# A604X.net
KiCad netlist of a schematic drawn in EAGLE
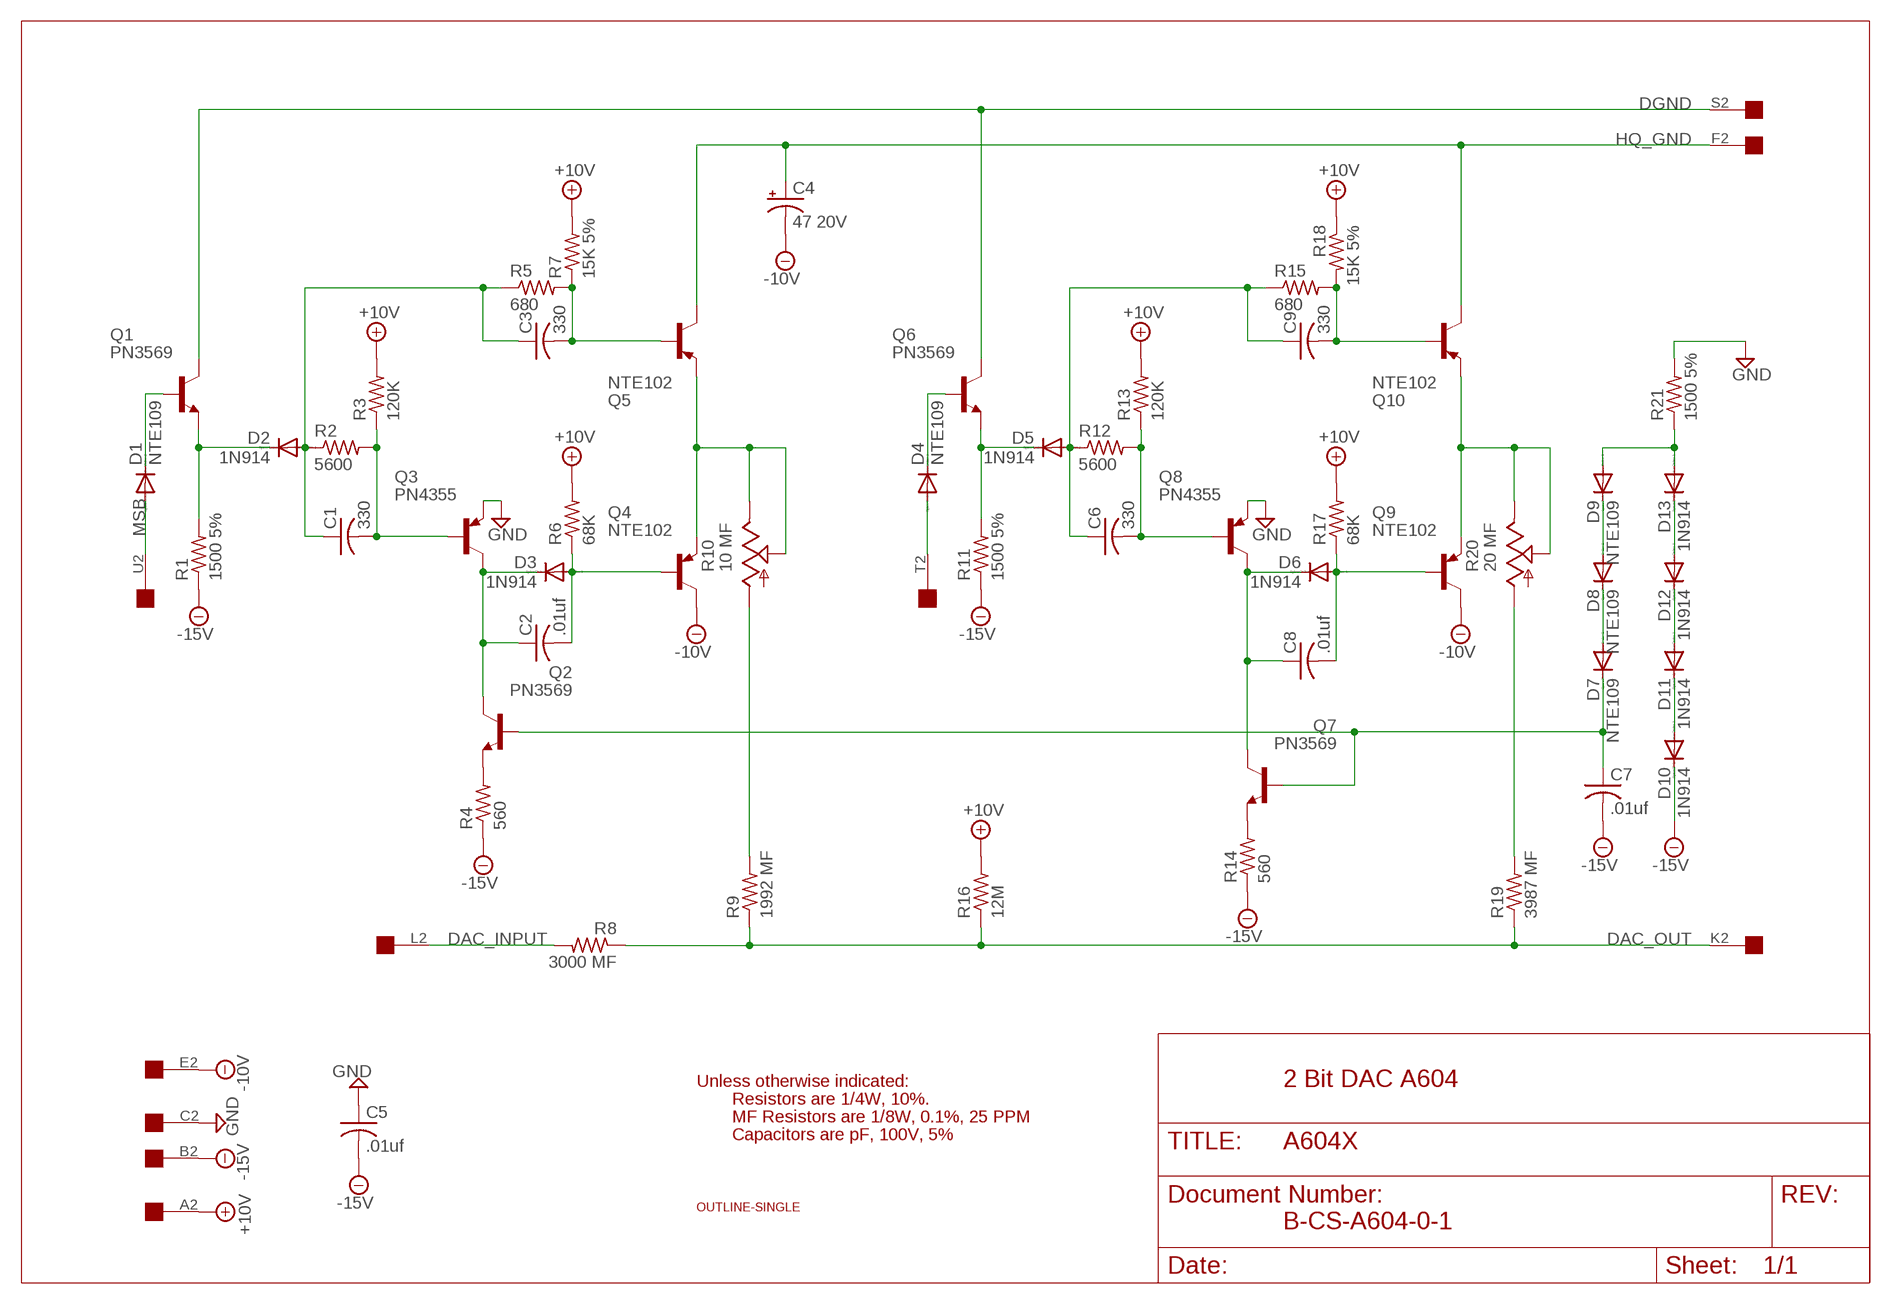
[diagram p0: schematic, sheet 1]

(export (version "E")
  (design (tool "Eeschema 10.0.6"))
  (components
    (comp (ref "C1")
      (value "330")
      (footprint "eagle-import:C075-032X103")
      (libsource (lib "eagle-import") (part "C-US075-032X103"))
    )
    (comp (ref "C2")
      (value ".01uf")
      (footprint "eagle-import:C050-025X075")
      (libsource (lib "eagle-import") (part "C-US050-025X075"))
    )
    (comp (ref "C3")
      (value "330")
      (footprint "eagle-import:C075-032X103")
      (libsource (lib "eagle-import") (part "C-US075-032X103"))
    )
    (comp (ref "C4")
      (value "47 20V")
      (footprint "eagle-import:E22-6")
      (libsource (lib "eagle-import") (part "CPOL-USE22-6AXIAL"))
    )
    (comp (ref "C5")
      (value ".01uf")
      (footprint "eagle-import:C050-025X075")
      (libsource (lib "eagle-import") (part "C-US050-025X075"))
    )
    (comp (ref "C6")
      (value "330")
      (footprint "eagle-import:C075-032X103")
      (libsource (lib "eagle-import") (part "C-US075-032X103"))
    )
    (comp (ref "C7")
      (value ".01uf")
      (footprint "eagle-import:C050-025X075")
      (libsource (lib "eagle-import") (part "C-US050-025X075"))
    )
    (comp (ref "C8")
      (value ".01uf")
      (footprint "eagle-import:C050-025X075")
      (libsource (lib "eagle-import") (part "C-US050-025X075"))
    )
    (comp (ref "C9")
      (value "330")
      (footprint "eagle-import:C075-032X103")
      (libsource (lib "eagle-import") (part "C-US075-032X103"))
    )
    (comp (ref "D1")
      (value "NTE109")
      (footprint "eagle-import:DO35-10")
      (libsource (lib "eagle-import") (part "1N4148DO35-10"))
    )
    (comp (ref "D2")
      (value "1N914")
      (footprint "eagle-import:DO35-10")
      (libsource (lib "eagle-import") (part "1N4148DO35-10"))
    )
    (comp (ref "D3")
      (value "1N914")
      (footprint "eagle-import:DO35-10")
      (libsource (lib "eagle-import") (part "1N4148DO35-10"))
    )
    (comp (ref "D4")
      (value "NTE109")
      (footprint "eagle-import:DO35-10")
      (libsource (lib "eagle-import") (part "1N4148DO35-10"))
    )
    (comp (ref "D5")
      (value "1N914")
      (footprint "eagle-import:DO35-10")
      (libsource (lib "eagle-import") (part "1N4148DO35-10"))
    )
    (comp (ref "D6")
      (value "1N914")
      (footprint "eagle-import:DO35-10")
      (libsource (lib "eagle-import") (part "1N4148DO35-10"))
    )
    (comp (ref "D7")
      (value "NTE109")
      (footprint "eagle-import:DO35-10")
      (libsource (lib "eagle-import") (part "1N4148DO35-10"))
    )
    (comp (ref "D8")
      (value "NTE109")
      (footprint "eagle-import:DO35-10")
      (libsource (lib "eagle-import") (part "1N4148DO35-10"))
    )
    (comp (ref "D9")
      (value "NTE109")
      (footprint "eagle-import:DO35-10")
      (libsource (lib "eagle-import") (part "1N4148DO35-10"))
    )
    (comp (ref "D10")
      (value "1N914")
      (footprint "eagle-import:DO35-10")
      (libsource (lib "eagle-import") (part "1N4148DO35-10"))
    )
    (comp (ref "D11")
      (value "1N914")
      (footprint "eagle-import:DO35-10")
      (libsource (lib "eagle-import") (part "1N4148DO35-10"))
    )
    (comp (ref "D12")
      (value "1N914")
      (footprint "eagle-import:DO35-10")
      (libsource (lib "eagle-import") (part "1N4148DO35-10"))
    )
    (comp (ref "D13")
      (value "1N914")
      (footprint "eagle-import:DO35-10")
      (libsource (lib "eagle-import") (part "1N4148DO35-10"))
    )
    (comp (ref "Q1")
      (value "PN3569")
      (footprint "eagle-import:TO39")
      (libsource (lib "eagle-import") (part "-NPN-TO39-EBC2N1613"))
    )
    (comp (ref "Q2")
      (value "PN3569")
      (footprint "eagle-import:TO39")
      (libsource (lib "eagle-import") (part "-NPN-TO39-EBC2N1613"))
    )
    (comp (ref "Q3")
      (value "PN4355")
      (footprint "eagle-import:TO39")
      (libsource (lib "eagle-import") (part "2N2904A"))
    )
    (comp (ref "Q4")
      (value "NTE102")
      (footprint "eagle-import:TO39")
      (libsource (lib "eagle-import") (part "2N2904A"))
    )
    (comp (ref "Q5")
      (value "NTE102")
      (footprint "eagle-import:TO39")
      (libsource (lib "eagle-import") (part "2N2904A"))
    )
    (comp (ref "Q6")
      (value "PN3569")
      (footprint "eagle-import:TO39")
      (libsource (lib "eagle-import") (part "-NPN-TO39-EBC2N1613"))
    )
    (comp (ref "Q7")
      (value "PN3569")
      (footprint "eagle-import:TO39")
      (libsource (lib "eagle-import") (part "-NPN-TO39-EBC2N1613"))
    )
    (comp (ref "Q8")
      (value "PN4355")
      (footprint "eagle-import:TO39")
      (libsource (lib "eagle-import") (part "2N2904A"))
    )
    (comp (ref "Q9")
      (value "NTE102")
      (footprint "eagle-import:TO39")
      (libsource (lib "eagle-import") (part "2N2904A"))
    )
    (comp (ref "Q10")
      (value "NTE102")
      (footprint "eagle-import:TO39")
      (libsource (lib "eagle-import") (part "2N2904A"))
    )
    (comp (ref "R1")
      (value "1500 5%")
      (footprint "eagle-import:0207_10")
      (libsource (lib "eagle-import") (part "R-US_0207/10"))
    )
    (comp (ref "R2")
      (value "5600")
      (footprint "eagle-import:0207_10")
      (libsource (lib "eagle-import") (part "R-US_0207/10"))
    )
    (comp (ref "R3")
      (value "120K")
      (footprint "eagle-import:0207_10")
      (libsource (lib "eagle-import") (part "R-US_0207/10"))
    )
    (comp (ref "R4")
      (value "560")
      (footprint "eagle-import:0207_10")
      (libsource (lib "eagle-import") (part "R-US_0207/10"))
    )
    (comp (ref "R5")
      (value "680")
      (footprint "eagle-import:0207_10")
      (libsource (lib "eagle-import") (part "R-US_0207/10"))
    )
    (comp (ref "R6")
      (value "68K")
      (footprint "eagle-import:0207_10")
      (libsource (lib "eagle-import") (part "R-US_0207/10"))
    )
    (comp (ref "R7")
      (value "15K 5%")
      (footprint "eagle-import:0207_10")
      (libsource (lib "eagle-import") (part "R-US_0207/10"))
    )
    (comp (ref "R8")
      (value "3000 MF")
      (footprint "eagle-import:0309_12")
      (libsource (lib "eagle-import") (part "R-US_0309/12"))
    )
    (comp (ref "R9")
      (value "1992 MF")
      (footprint "eagle-import:0309_12")
      (libsource (lib "eagle-import") (part "R-US_0309/12"))
    )
    (comp (ref "R10")
      (value "10 MF")
      (footprint "eagle-import:S75P")
      (libsource (lib "eagle-import") (part "TRIM_US-S75P"))
    )
    (comp (ref "R11")
      (value "1500 5%")
      (footprint "eagle-import:0207_10")
      (libsource (lib "eagle-import") (part "R-US_0207/10"))
    )
    (comp (ref "R12")
      (value "5600")
      (footprint "eagle-import:0207_10")
      (libsource (lib "eagle-import") (part "R-US_0207/10"))
    )
    (comp (ref "R13")
      (value "120K")
      (footprint "eagle-import:0207_10")
      (libsource (lib "eagle-import") (part "R-US_0207/10"))
    )
    (comp (ref "R14")
      (value "560")
      (footprint "eagle-import:0207_10")
      (libsource (lib "eagle-import") (part "R-US_0207/10"))
    )
    (comp (ref "R15")
      (value "680")
      (footprint "eagle-import:0207_10")
      (libsource (lib "eagle-import") (part "R-US_0207/10"))
    )
    (comp (ref "R16")
      (value "12M")
      (footprint "eagle-import:0207_10")
      (libsource (lib "eagle-import") (part "R-US_0207/10"))
    )
    (comp (ref "R17")
      (value "68K")
      (footprint "eagle-import:0207_10")
      (libsource (lib "eagle-import") (part "R-US_0207/10"))
    )
    (comp (ref "R18")
      (value "15K 5%")
      (footprint "eagle-import:0207_10")
      (libsource (lib "eagle-import") (part "R-US_0207/10"))
    )
    (comp (ref "R19")
      (value "3987 MF")
      (footprint "eagle-import:0309_12")
      (libsource (lib "eagle-import") (part "R-US_0309/12"))
    )
    (comp (ref "R20")
      (value "20 MF")
      (footprint "eagle-import:S75P")
      (libsource (lib "eagle-import") (part "TRIM_US-S75P"))
    )
    (comp (ref "R21")
      (value "1500 5%")
      (footprint "eagle-import:0207_10")
      (libsource (lib "eagle-import") (part "R-US_0207/10"))
    )
    (comp (ref "U$1")
      (value "OUTLINE-SINGLE")
      (footprint "eagle-import:SINGLE")
      (libsource (lib "eagle-import") (part "OUTLINE-SINGLE"))
    )
    (comp (ref "U$3")
      (value "EDGE-1")
      (footprint "eagle-import:EDGE-CON1")
      (libsource (lib "eagle-import") (part "EDGE-1"))
    )
  )
  (nets
    (net (code "1") (name "+10V") (class "Default")
      (node (ref "R13") (pin "2") (pinfunction "2_2") (pintype "passive"))
      (node (ref "R16") (pin "2") (pinfunction "2_2") (pintype "passive"))
      (node (ref "R17") (pin "2") (pinfunction "2_2") (pintype "passive"))
      (node (ref "R18") (pin "1") (pinfunction "1_1") (pintype "passive"))
      (node (ref "R3") (pin "2") (pinfunction "2_2") (pintype "passive"))
      (node (ref "R6") (pin "2") (pinfunction "2_2") (pintype "passive"))
      (node (ref "R7") (pin "2") (pinfunction "2_2") (pintype "passive"))
      (node (ref "U$3") (pin "A2") (pinfunction "1_A2") (pintype "bidirectional"))
    )
    (net (code "2") (name "-10V") (class "Default")
      (node (ref "C4") (pin "-") (pinfunction "-_-") (pintype "passive"))
      (node (ref "Q4") (pin "3") (pinfunction "C_3") (pintype "passive"))
      (node (ref "Q9") (pin "3") (pinfunction "C_3") (pintype "passive"))
      (node (ref "U$3") (pin "E2") (pinfunction "1_E2") (pintype "bidirectional"))
    )
    (net (code "3") (name "-15V") (class "Default")
      (node (ref "C5") (pin "2") (pinfunction "2_2") (pintype "passive"))
      (node (ref "C7") (pin "2") (pinfunction "2_2") (pintype "passive"))
      (node (ref "D10") (pin "C") (pinfunction "C_C") (pintype "passive"))
      (node (ref "R1") (pin "1") (pinfunction "1_1") (pintype "passive"))
      (node (ref "R11") (pin "1") (pinfunction "1_1") (pintype "passive"))
      (node (ref "R14") (pin "1") (pinfunction "1_1") (pintype "passive"))
      (node (ref "R4") (pin "1") (pinfunction "1_1") (pintype "passive"))
      (node (ref "U$3") (pin "B2") (pinfunction "1_B2") (pintype "bidirectional"))
    )
    (net (code "4") (name "/DAC_INPUT") (class "Default")
      (node (ref "R8") (pin "2") (pinfunction "2_2") (pintype "passive"))
      (node (ref "U$3") (pin "L2") (pinfunction "1_L2") (pintype "bidirectional"))
    )
    (net (code "5") (name "/DAC_OUT") (class "Default")
      (node (ref "R16") (pin "1") (pinfunction "1_1") (pintype "passive"))
      (node (ref "R19") (pin "1") (pinfunction "1_1") (pintype "passive"))
      (node (ref "R8") (pin "1") (pinfunction "1_1") (pintype "passive"))
      (node (ref "R9") (pin "1") (pinfunction "1_1") (pintype "passive"))
      (node (ref "U$3") (pin "K2") (pinfunction "1_K2") (pintype "bidirectional"))
    )
    (net (code "6") (name "/DGND") (class "Default")
      (node (ref "Q1") (pin "3") (pinfunction "C_3") (pintype "passive"))
      (node (ref "Q6") (pin "3") (pinfunction "C_3") (pintype "passive"))
      (node (ref "U$3") (pin "S2") (pinfunction "1_S2") (pintype "bidirectional"))
    )
    (net (code "7") (name "/HQ_GND") (class "Default")
      (node (ref "C4") (pin "+") (pinfunction "+_+") (pintype "passive"))
      (node (ref "Q10") (pin "3") (pinfunction "C_3") (pintype "passive"))
      (node (ref "Q5") (pin "3") (pinfunction "C_3") (pintype "passive"))
      (node (ref "U$3") (pin "F2") (pinfunction "1_F2") (pintype "bidirectional"))
    )
    (net (code "8") (name "/MSB") (class "Default")
      (node (ref "D1") (pin "A") (pinfunction "A_A") (pintype "passive"))
      (node (ref "U$3") (pin "U2") (pinfunction "1_U2") (pintype "bidirectional"))
    )
    (net (code "9") (name "GND") (class "Default")
      (node (ref "C5") (pin "1") (pinfunction "1_1") (pintype "passive"))
      (node (ref "Q3") (pin "1") (pinfunction "E_1") (pintype "passive"))
      (node (ref "Q8") (pin "1") (pinfunction "E_1") (pintype "passive"))
      (node (ref "R21") (pin "2") (pinfunction "2_2") (pintype "passive"))
      (node (ref "U$3") (pin "C2") (pinfunction "1_C2") (pintype "bidirectional"))
    )
    (net (code "10") (name "Net-(C1-Pad1)") (class "Default")
      (node (ref "C1") (pin "1") (pinfunction "1_1") (pintype "passive"))
      (node (ref "C3") (pin "1") (pinfunction "1_1") (pintype "passive"))
      (node (ref "D2") (pin "A") (pinfunction "A_A") (pintype "passive"))
      (node (ref "R2") (pin "1") (pinfunction "1_1") (pintype "passive"))
      (node (ref "R5") (pin "1") (pinfunction "1_1") (pintype "passive"))
    )
    (net (code "11") (name "Net-(C6-Pad1)") (class "Default")
      (node (ref "C6") (pin "1") (pinfunction "1_1") (pintype "passive"))
      (node (ref "C9") (pin "1") (pinfunction "1_1") (pintype "passive"))
      (node (ref "D5") (pin "A") (pinfunction "A_A") (pintype "passive"))
      (node (ref "R12") (pin "1") (pinfunction "1_1") (pintype "passive"))
      (node (ref "R15") (pin "1") (pinfunction "1_1") (pintype "passive"))
    )
    (net (code "12") (name "Net-(D7-PadA)") (class "Default")
      (node (ref "D7") (pin "A") (pinfunction "A_A") (pintype "passive"))
      (node (ref "D8") (pin "C") (pinfunction "C_C") (pintype "passive"))
    )
    (net (code "13") (name "Net-(D8-PadA)") (class "Default")
      (node (ref "D8") (pin "A") (pinfunction "A_A") (pintype "passive"))
      (node (ref "D9") (pin "C") (pinfunction "C_C") (pintype "passive"))
    )
    (net (code "14") (name "Net-(D10-PadA)") (class "Default")
      (node (ref "D10") (pin "A") (pinfunction "A_A") (pintype "passive"))
      (node (ref "D11") (pin "C") (pinfunction "C_C") (pintype "passive"))
    )
    (net (code "15") (name "Net-(D11-PadA)") (class "Default")
      (node (ref "D11") (pin "A") (pinfunction "A_A") (pintype "passive"))
      (node (ref "D12") (pin "C") (pinfunction "C_C") (pintype "passive"))
    )
    (net (code "16") (name "Net-(D12-PadA)") (class "Default")
      (node (ref "D12") (pin "A") (pinfunction "A_A") (pintype "passive"))
      (node (ref "D13") (pin "C") (pinfunction "C_C") (pintype "passive"))
    )
    (net (code "17") (name "Net-(D13-PadA)") (class "Default")
      (node (ref "D13") (pin "A") (pinfunction "A_A") (pintype "passive"))
      (node (ref "D9") (pin "A") (pinfunction "A_A") (pintype "passive"))
      (node (ref "R21") (pin "1") (pinfunction "1_1") (pintype "passive"))
    )
    (net (code "18") (name "Net-(Q1-B)") (class "Default")
      (node (ref "D1") (pin "C") (pinfunction "C_C") (pintype "passive"))
      (node (ref "Q1") (pin "2") (pinfunction "B_2") (pintype "passive"))
    )
    (net (code "19") (name "Net-(Q1-E)") (class "Default")
      (node (ref "D2") (pin "C") (pinfunction "C_C") (pintype "passive"))
      (node (ref "Q1") (pin "1") (pinfunction "E_1") (pintype "passive"))
      (node (ref "R1") (pin "2") (pinfunction "2_2") (pintype "passive"))
    )
    (net (code "20") (name "Net-(Q2-B)") (class "Default")
      (node (ref "C7") (pin "1") (pinfunction "1_1") (pintype "passive"))
      (node (ref "D7") (pin "C") (pinfunction "C_C") (pintype "passive"))
      (node (ref "Q2") (pin "2") (pinfunction "B_2") (pintype "passive"))
      (node (ref "Q7") (pin "2") (pinfunction "B_2") (pintype "passive"))
    )
    (net (code "21") (name "Net-(Q2-C)") (class "Default")
      (node (ref "C2") (pin "1") (pinfunction "1_1") (pintype "passive"))
      (node (ref "D3") (pin "C") (pinfunction "C_C") (pintype "passive"))
      (node (ref "Q2") (pin "3") (pinfunction "C_3") (pintype "passive"))
      (node (ref "Q3") (pin "3") (pinfunction "C_3") (pintype "passive"))
    )
    (net (code "22") (name "Net-(Q2-E)") (class "Default")
      (node (ref "Q2") (pin "1") (pinfunction "E_1") (pintype "passive"))
      (node (ref "R4") (pin "2") (pinfunction "2_2") (pintype "passive"))
    )
    (net (code "23") (name "Net-(Q3-B)") (class "Default")
      (node (ref "C1") (pin "2") (pinfunction "2_2") (pintype "passive"))
      (node (ref "Q3") (pin "2") (pinfunction "B_2") (pintype "passive"))
      (node (ref "R2") (pin "2") (pinfunction "2_2") (pintype "passive"))
      (node (ref "R3") (pin "1") (pinfunction "1_1") (pintype "passive"))
    )
    (net (code "24") (name "Net-(Q4-B)") (class "Default")
      (node (ref "C2") (pin "2") (pinfunction "2_2") (pintype "passive"))
      (node (ref "D3") (pin "A") (pinfunction "A_A") (pintype "passive"))
      (node (ref "Q4") (pin "2") (pinfunction "B_2") (pintype "passive"))
      (node (ref "R6") (pin "1") (pinfunction "1_1") (pintype "passive"))
    )
    (net (code "25") (name "Net-(Q4-E)") (class "Default")
      (node (ref "Q4") (pin "1") (pinfunction "E_1") (pintype "passive"))
      (node (ref "Q5") (pin "1") (pinfunction "E_1") (pintype "passive"))
      (node (ref "R10") (pin "E") (pinfunction "E_E") (pintype "passive"))
      (node (ref "R10") (pin "S") (pinfunction "S_S") (pintype "passive"))
    )
    (net (code "26") (name "Net-(Q5-B)") (class "Default")
      (node (ref "C3") (pin "2") (pinfunction "2_2") (pintype "passive"))
      (node (ref "Q5") (pin "2") (pinfunction "B_2") (pintype "passive"))
      (node (ref "R5") (pin "2") (pinfunction "2_2") (pintype "passive"))
      (node (ref "R7") (pin "1") (pinfunction "1_1") (pintype "passive"))
    )
    (net (code "27") (name "Net-(Q6-B)") (class "Default")
      (node (ref "D4") (pin "C") (pinfunction "C_C") (pintype "passive"))
      (node (ref "Q6") (pin "2") (pinfunction "B_2") (pintype "passive"))
    )
    (net (code "28") (name "Net-(Q6-E)") (class "Default")
      (node (ref "D5") (pin "C") (pinfunction "C_C") (pintype "passive"))
      (node (ref "Q6") (pin "1") (pinfunction "E_1") (pintype "passive"))
      (node (ref "R11") (pin "2") (pinfunction "2_2") (pintype "passive"))
    )
    (net (code "29") (name "Net-(Q7-C)") (class "Default")
      (node (ref "C8") (pin "1") (pinfunction "1_1") (pintype "passive"))
      (node (ref "D6") (pin "C") (pinfunction "C_C") (pintype "passive"))
      (node (ref "Q7") (pin "3") (pinfunction "C_3") (pintype "passive"))
      (node (ref "Q8") (pin "3") (pinfunction "C_3") (pintype "passive"))
    )
    (net (code "30") (name "Net-(Q7-E)") (class "Default")
      (node (ref "Q7") (pin "1") (pinfunction "E_1") (pintype "passive"))
      (node (ref "R14") (pin "2") (pinfunction "2_2") (pintype "passive"))
    )
    (net (code "31") (name "Net-(Q8-B)") (class "Default")
      (node (ref "C6") (pin "2") (pinfunction "2_2") (pintype "passive"))
      (node (ref "Q8") (pin "2") (pinfunction "B_2") (pintype "passive"))
      (node (ref "R12") (pin "2") (pinfunction "2_2") (pintype "passive"))
      (node (ref "R13") (pin "1") (pinfunction "1_1") (pintype "passive"))
    )
    (net (code "32") (name "Net-(Q9-B)") (class "Default")
      (node (ref "C8") (pin "2") (pinfunction "2_2") (pintype "passive"))
      (node (ref "D6") (pin "A") (pinfunction "A_A") (pintype "passive"))
      (node (ref "Q9") (pin "2") (pinfunction "B_2") (pintype "passive"))
      (node (ref "R17") (pin "1") (pinfunction "1_1") (pintype "passive"))
    )
    (net (code "33") (name "Net-(Q10-B)") (class "Default")
      (node (ref "C9") (pin "2") (pinfunction "2_2") (pintype "passive"))
      (node (ref "Q10") (pin "2") (pinfunction "B_2") (pintype "passive"))
      (node (ref "R15") (pin "2") (pinfunction "2_2") (pintype "passive"))
      (node (ref "R18") (pin "2") (pinfunction "2_2") (pintype "passive"))
    )
    (net (code "34") (name "Net-(Q10-E)") (class "Default")
      (node (ref "Q10") (pin "1") (pinfunction "E_1") (pintype "passive"))
      (node (ref "Q9") (pin "1") (pinfunction "E_1") (pintype "passive"))
      (node (ref "R20") (pin "E") (pinfunction "E_E") (pintype "passive"))
      (node (ref "R20") (pin "S") (pinfunction "S_S") (pintype "passive"))
    )
    (net (code "35") (name "Net-(R10-PadA)") (class "Default")
      (node (ref "R10") (pin "A") (pinfunction "A_A") (pintype "passive"))
      (node (ref "R9") (pin "2") (pinfunction "2_2") (pintype "passive"))
    )
    (net (code "36") (name "Net-(R19-Pad2)") (class "Default")
      (node (ref "R19") (pin "2") (pinfunction "2_2") (pintype "passive"))
      (node (ref "R20") (pin "A") (pinfunction "A_A") (pintype "passive"))
    )
    (net (code "37") (name "Net-(U$3P-1)") (class "Default")
      (node (ref "D4") (pin "A") (pinfunction "A_A") (pintype "passive"))
      (node (ref "U$3") (pin "T2") (pinfunction "1_T2") (pintype "bidirectional"))
    )
  )
)
